# Ganancia.net
KiCad netlist of a schematic drawn in Altium Designer
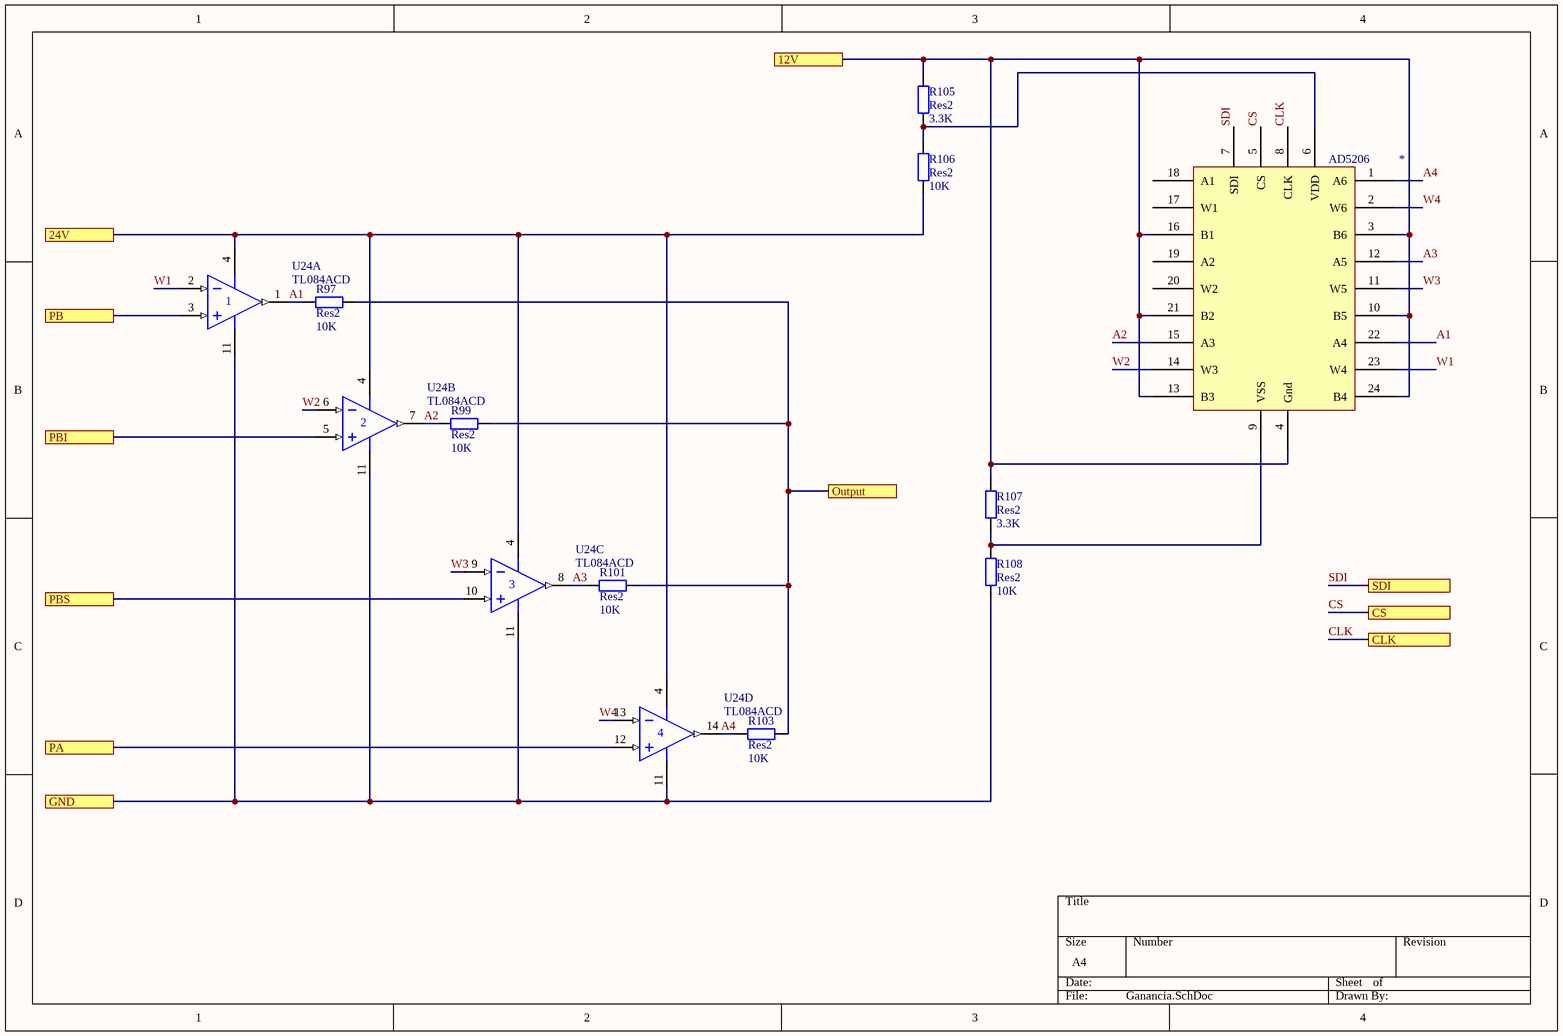
[diagram p0: Ganancia.SchDoc]

(export (version "E")
  (design (tool "Eeschema 10.0.6"))
  (components
    (comp (ref "*") (value "AD5206") (footprint "DIP-24/D31") (libsource (lib "XR2206") (part "AD5206")))
    (comp (ref "R97")
      (value "Res2")
      (footprint "1206 resistor")
      (description "Resistor")
      (fields (field (name "ALTIUM_VALUE") "10K") (field (name "PUBLISHER") "Altium Limited"))
      (libsource (lib "") (part "Res2_1"))
    )
    (comp (ref "R99")
      (value "Res2")
      (footprint "1206 resistor")
      (description "Resistor")
      (fields (field (name "ALTIUM_VALUE") "10K") (field (name "PUBLISHER") "Altium Limited"))
      (libsource (lib "") (part "Res2_1"))
    )
    (comp (ref "R101")
      (value "Res2")
      (footprint "1206 resistor")
      (description "Resistor")
      (fields (field (name "ALTIUM_VALUE") "10K") (field (name "PUBLISHER") "Altium Limited"))
      (libsource (lib "") (part "Res2_1"))
    )
    (comp (ref "R103")
      (value "Res2")
      (footprint "1206 resistor")
      (description "Resistor")
      (fields (field (name "ALTIUM_VALUE") "10K") (field (name "PUBLISHER") "Altium Limited"))
      (libsource (lib "") (part "Res2_1"))
    )
    (comp (ref "R105")
      (value "Res2")
      (footprint "1206 resistor")
      (description "Resistor")
      (fields (field (name "ALTIUM_VALUE") "3.3K") (field (name "PUBLISHER") "Altium Limited"))
      (libsource (lib "Miscellaneous Devices") (part "Res2"))
    )
    (comp (ref "R106")
      (value "Res2")
      (footprint "1206 resistor")
      (description "Resistor")
      (fields (field (name "ALTIUM_VALUE") "10K") (field (name "PUBLISHER") "Altium Limited"))
      (libsource (lib "Miscellaneous Devices") (part "Res2"))
    )
    (comp (ref "R107")
      (value "Res2")
      (footprint "1206 resistor")
      (description "Resistor")
      (fields (field (name "ALTIUM_VALUE") "3.3K") (field (name "PUBLISHER") "Altium Limited"))
      (libsource (lib "Miscellaneous Devices") (part "Res2"))
    )
    (comp (ref "R108")
      (value "Res2")
      (footprint "1206 resistor")
      (description "Resistor")
      (fields (field (name "ALTIUM_VALUE") "10K") (field (name "PUBLISHER") "Altium Limited"))
      (libsource (lib "Miscellaneous Devices") (part "Res2"))
    )
    (comp (ref "U24")
      (value "TL084ACD")
      (footprint "751A-02_N")
      (description "JFET-Input Operational Amplifier")
      (fields (field (name "PUBLISHER") "Altium Limited"))
      (libsource (lib "Motorola Amplifier Operational Amplifier") (part "TL084ACD"))
    )
  )
  (nets
    (net (code "1") (name "/12V") (class "Default")
      (node (ref "*") (pin "10") (pinfunction "B5_10") (pintype "passive"))
      (node (ref "*") (pin "13") (pinfunction "B3_13") (pintype "passive"))
      (node (ref "*") (pin "16") (pinfunction "B1_16") (pintype "passive"))
      (node (ref "*") (pin "21") (pinfunction "B2_21") (pintype "passive"))
      (node (ref "*") (pin "24") (pinfunction "B4_24") (pintype "passive"))
      (node (ref "*") (pin "3") (pinfunction "B6_3") (pintype "passive"))
      (node (ref "*") (pin "4") (pinfunction "Gnd_4") (pintype "passive"))
      (node (ref "R105") (pin "2") (pinfunction "2_2") (pintype "passive"))
      (node (ref "R107") (pin "2") (pinfunction "2_2") (pintype "passive"))
    )
    (net (code "2") (name "/24V") (class "Default")
      (node (ref "R106") (pin "1") (pinfunction "1_1") (pintype "passive"))
      (node (ref "U24") (pin "4") (pinfunction "V+_4") (pintype "power_in"))
    )
    (net (code "3") (name "/A1") (class "Default")
      (node (ref "*") (pin "22") (pinfunction "A4_22") (pintype "passive"))
      (node (ref "R97") (pin "1") (pinfunction "1_1") (pintype "passive"))
      (node (ref "U24") (pin "1") (pinfunction "OUT_1") (pintype "output"))
    )
    (net (code "4") (name "/A2") (class "Default")
      (node (ref "*") (pin "15") (pinfunction "A3_15") (pintype "passive"))
      (node (ref "R99") (pin "1") (pinfunction "1_1") (pintype "passive"))
      (node (ref "U24") (pin "7") (pinfunction "OUT_7") (pintype "output"))
    )
    (net (code "5") (name "/A3") (class "Default")
      (node (ref "*") (pin "12") (pinfunction "A5_12") (pintype "passive"))
      (node (ref "R101") (pin "1") (pinfunction "1_1") (pintype "passive"))
      (node (ref "U24") (pin "8") (pinfunction "OUT_8") (pintype "output"))
    )
    (net (code "6") (name "/A4") (class "Default")
      (node (ref "*") (pin "1") (pinfunction "A6_1") (pintype "passive"))
      (node (ref "R103") (pin "1") (pinfunction "1_1") (pintype "passive"))
      (node (ref "U24") (pin "14") (pinfunction "OUT_14") (pintype "output"))
    )
    (net (code "7") (name "/CLK") (class "Default")
      (node (ref "*") (pin "8") (pinfunction "CLK_8") (pintype "passive"))
    )
    (net (code "8") (name "/CS") (class "Default")
      (node (ref "*") (pin "5") (pinfunction "CS_5") (pintype "passive"))
    )
    (net (code "9") (name "/GND") (class "Default")
      (node (ref "R108") (pin "1") (pinfunction "1_1") (pintype "passive"))
      (node (ref "U24") (pin "11") (pinfunction "V-_11") (pintype "power_in"))
    )
    (net (code "10") (name "/Output") (class "Default")
      (node (ref "R101") (pin "2") (pinfunction "2_2") (pintype "passive"))
      (node (ref "R103") (pin "2") (pinfunction "2_2") (pintype "passive"))
      (node (ref "R97") (pin "2") (pinfunction "2_2") (pintype "passive"))
      (node (ref "R99") (pin "2") (pinfunction "2_2") (pintype "passive"))
    )
    (net (code "11") (name "/PA") (class "Default")
      (node (ref "U24") (pin "12") (pinfunction "IN+_12") (pintype "input"))
    )
    (net (code "12") (name "/PB") (class "Default")
      (node (ref "U24") (pin "3") (pinfunction "IN+_3") (pintype "input"))
    )
    (net (code "13") (name "/PBI") (class "Default")
      (node (ref "U24") (pin "5") (pinfunction "IN+_5") (pintype "input"))
    )
    (net (code "14") (name "/PBS") (class "Default")
      (node (ref "U24") (pin "10") (pinfunction "IN+_10") (pintype "input"))
    )
    (net (code "15") (name "/SDI") (class "Default")
      (node (ref "*") (pin "7") (pinfunction "SDI_7") (pintype "passive"))
    )
    (net (code "16") (name "/W1") (class "Default")
      (node (ref "*") (pin "23") (pinfunction "W4_23") (pintype "passive"))
      (node (ref "U24") (pin "2") (pinfunction "IN-_2") (pintype "input"))
    )
    (net (code "17") (name "/W2") (class "Default")
      (node (ref "*") (pin "14") (pinfunction "W3_14") (pintype "passive"))
      (node (ref "U24") (pin "6") (pinfunction "IN-_6") (pintype "input"))
    )
    (net (code "18") (name "/W3") (class "Default")
      (node (ref "*") (pin "11") (pinfunction "W5_11") (pintype "passive"))
      (node (ref "U24") (pin "9") (pinfunction "IN-_9") (pintype "input"))
    )
    (net (code "19") (name "/W4") (class "Default")
      (node (ref "*") (pin "2") (pinfunction "W6_2") (pintype "passive"))
      (node (ref "U24") (pin "13") (pinfunction "IN-_13") (pintype "input"))
    )
    (net (code "20") (name "Net-(*-VDD)") (class "Default")
      (node (ref "*") (pin "6") (pinfunction "VDD_6") (pintype "passive"))
      (node (ref "R105") (pin "1") (pinfunction "1_1") (pintype "passive"))
      (node (ref "R106") (pin "2") (pinfunction "2_2") (pintype "passive"))
    )
    (net (code "21") (name "Net-(*-VSS)") (class "Default")
      (node (ref "*") (pin "9") (pinfunction "VSS_9") (pintype "passive"))
      (node (ref "R107") (pin "1") (pinfunction "1_1") (pintype "passive"))
      (node (ref "R108") (pin "2") (pinfunction "2_2") (pintype "passive"))
    )
    (net (code "22") (name "unconnected-(*-A1-Pad18)") (class "Default")
      (node (ref "*") (pin "18") (pinfunction "A1_18") (pintype "passive"))
    )
    (net (code "23") (name "unconnected-(*-A2-Pad19)") (class "Default")
      (node (ref "*") (pin "19") (pinfunction "A2_19") (pintype "passive"))
    )
    (net (code "24") (name "unconnected-(*-W1-Pad17)") (class "Default")
      (node (ref "*") (pin "17") (pinfunction "W1_17") (pintype "passive"))
    )
    (net (code "25") (name "unconnected-(*-W2-Pad20)") (class "Default")
      (node (ref "*") (pin "20") (pinfunction "W2_20") (pintype "passive"))
    )
  )
)
